# power.net
KiCad netlist of a schematic drawn in Altium Designer
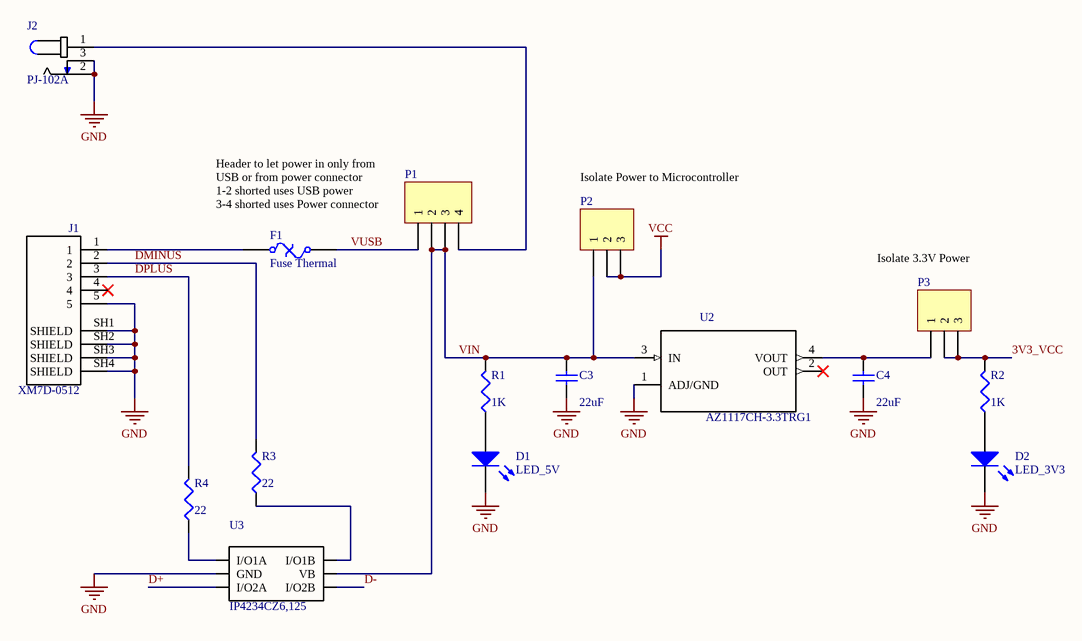
[diagram p0: power.SchDoc]

(export (version "E")
  (design (tool "Eeschema 10.0.6"))
  (components
    (comp (ref "C3")
      (value "22uF")
      (footprint "C1206")
      (description "Capacitor (Semiconductor SIM Model)")
      (fields
        (field (name "DIGIKEYPARTNO") "1276-3300-1-ND")
        (field (name "Comment") "Cap Semi")
        (field (name "PUBLISHER") "Altium Limited")
      )
      (libsource (lib "Miscellaneous Devices") (part "Cap Semi"))
    )
    (comp (ref "C4")
      (value "22uF")
      (footprint "C1206")
      (description "Capacitor (Semiconductor SIM Model)")
      (fields
        (field (name "DIGIKEYPARTNO") "1276-3300-1-ND")
        (field (name "Comment") "Cap Semi")
        (field (name "PUBLISHER") "Altium Limited")
      )
      (libsource (lib "Miscellaneous Devices") (part "Cap Semi"))
    )
    (comp (ref "D1")
      (value "LED_5V")
      (footprint "3.2X1.6X1.1")
      (description "Typical RED, GREEN, YELLOW, AMBER GaAs LED")
      (fields (field (name "PUBLISHER") "Altium Limited"))
      (libsource (lib "Miscellaneous Devices") (part "LED2"))
    )
    (comp (ref "D2")
      (value "LED_3V3")
      (footprint "3.2X1.6X1.1")
      (description "Typical RED, GREEN, YELLOW, AMBER GaAs LED")
      (fields (field (name "PUBLISHER") "Altium Limited"))
      (libsource (lib "Miscellaneous Devices") (part "LED2"))
    )
    (comp (ref "F1")
      (value "Fuse Thermal")
      (footprint "1812")
      (description "Thermal Fuse")
      (fields
        (field (name "MANUFACTURERPARTNO") "MF-MSMF050-2")
        (field (name "DIGIKEYPARTNO") "MF-MSMF050-2CT-ND")
        (field (name "PUBLISHER") "Altium Limited")
      )
      (libsource (lib "Miscellaneous Devices") (part "Fuse Thermal"))
    )
    (comp (ref "J1")
      (value "XM7D-0512")
      (footprint "*OMRON_XM7D-0512_XM7D-0512(Primary)")
      (description "Conn Mini USB Type B SKT 5 POS 0.8mm Solder RA Thru-Hole 5 Terminal 1 Port")
      (fields (field (name "MF") "Omron Electronics"))
      (libsource (lib "XM7D-0512") (part "XM7D-0512"))
    )
    (comp (ref "J2")
      (value "PJ-102A")
      (footprint "*CUI_PJ-102A")
      (description "2.0 mm Center Pin, 2.5 A, Right Angle, Through Hole, Tapered Pins, Dc Power Jack Connector")
      (fields (field (name "MF") "CUI Inc."))
      (libsource (lib "PJ-102A") (part "PJ-102A"))
    )
    (comp (ref "P1")
      (value "Header 4")
      (footprint "HDR1X4")
      (description "Header, 4-Pin")
      (fields (field (name "PUBLISHER") "Altium Limited"))
      (libsource (lib "Miscellaneous Connectors") (part "Header 4"))
    )
    (comp (ref "P2")
      (value "ON   OFF")
      (footprint "HDR1X3")
      (description "Header, 3-Pin")
      (fields (field (name "PUBLISHER") "Altium Limited"))
      (libsource (lib "Miscellaneous Connectors") (part "Header 3"))
    )
    (comp (ref "P3")
      (value "3.3 NC")
      (footprint "HDR1X3")
      (description "Header, 3-Pin")
      (fields (field (name "PUBLISHER") "Altium Limited"))
      (libsource (lib "Miscellaneous Connectors") (part "Header 3"))
    )
    (comp (ref "R1")
      (value "1K")
      (footprint "C1206")
      (description "Resistor")
      (fields (field (name "Comment") "Res3") (field (name "PUBLISHER") "Altium Limited"))
      (libsource (lib "Miscellaneous Devices") (part "Res3"))
    )
    (comp (ref "R2")
      (value "1K")
      (footprint "C1206")
      (description "Resistor")
      (fields (field (name "Comment") "Res3") (field (name "PUBLISHER") "Altium Limited"))
      (libsource (lib "Miscellaneous Devices") (part "Res3"))
    )
    (comp (ref "R3")
      (value "22")
      (footprint "C1206")
      (description "Resistor")
      (fields (field (name "Comment") "Res3") (field (name "PUBLISHER") "Altium Limited"))
      (libsource (lib "Miscellaneous Devices") (part "Res3"))
    )
    (comp (ref "R4")
      (value "22")
      (footprint "C1206")
      (description "Resistor")
      (fields (field (name "Comment") "Res3") (field (name "PUBLISHER") "Altium Limited"))
      (libsource (lib "Miscellaneous Devices") (part "Res3"))
    )
    (comp (ref "U2")
      (value "AZ1117CH-3.3TRG1")
      (footprint "*SOT230P696X180-4N")
      (description "Voltage stabiliser; LDO, fixed; 3.3V; 0.8A; SOT223; SMD")
      (fields
        (field (name "MF") "Diodes Incorporated")
        (field (name "DIGIKEYPARTNO") "AZ1117CH-3.3TRG1DICT-ND")
      )
      (libsource (lib "LM1117MP-3.3") (part "LM1117MP-3.3"))
    )
    (comp (ref "U3")
      (value "IP4234CZ6,125")
      (footprint "*SOT-457")
      (description "DIODE, ESD TVS, USB2.0, SOT457; Operating Voltage: 3V; No. of Pins: 6; SVHC: No SVHC _18-Jun-2010_")
      (fields (field (name "MF") "NXP Semiconductors"))
      (libsource (lib "IP4234CZ6") (part "IP4234CZ6"))
    )
  )
  (nets
    (net (code "1") (name "/3V3_VCC") (class "Default")
      (node (ref "P3") (pin "2") (pinfunction "2_2") (pintype "passive"))
      (node (ref "P3") (pin "3") (pinfunction "3_3") (pintype "passive"))
      (node (ref "R2") (pin "2") (pinfunction "2_2") (pintype "passive"))
    )
    (net (code "2") (name "/D+") (class "Default")
      (node (ref "U3") (pin "3") (pinfunction "I/O2A_3") (pintype "bidirectional"))
    )
    (net (code "3") (name "/D-") (class "Default")
      (node (ref "U3") (pin "4") (pinfunction "I/O2B_4") (pintype "bidirectional"))
    )
    (net (code "4") (name "/DMINUS") (class "Default")
      (node (ref "J1") (pin "2") (pinfunction "2_2") (pintype "passive"))
      (node (ref "R3") (pin "2") (pinfunction "2_2") (pintype "passive"))
    )
    (net (code "5") (name "/DPLUS") (class "Default")
      (node (ref "J1") (pin "3") (pinfunction "3_3") (pintype "passive"))
      (node (ref "R4") (pin "2") (pinfunction "2_2") (pintype "passive"))
    )
    (net (code "6") (name "/VIN") (class "Default")
      (node (ref "C3") (pin "2") (pinfunction "2_2") (pintype "passive"))
      (node (ref "P1") (pin "2") (pinfunction "2_2") (pintype "passive"))
      (node (ref "P1") (pin "3") (pinfunction "3_3") (pintype "passive"))
      (node (ref "P2") (pin "1") (pinfunction "1_1") (pintype "passive"))
      (node (ref "R1") (pin "2") (pinfunction "2_2") (pintype "passive"))
      (node (ref "U2") (pin "3") (pinfunction "IN_3") (pintype "input"))
      (node (ref "U3") (pin "5") (pinfunction "VB_5") (pintype "bidirectional"))
    )
    (net (code "7") (name "/VUSB") (class "Default")
      (node (ref "F1") (pin "2") (pinfunction "2_2") (pintype "passive"))
      (node (ref "P1") (pin "1") (pinfunction "1_1") (pintype "passive"))
    )
    (net (code "8") (name "GND") (class "Default")
      (node (ref "C3") (pin "1") (pinfunction "1_1") (pintype "passive"))
      (node (ref "C4") (pin "1") (pinfunction "1_1") (pintype "passive"))
      (node (ref "D1") (pin "2") (pinfunction "K_2") (pintype "passive"))
      (node (ref "D2") (pin "2") (pinfunction "K_2") (pintype "passive"))
      (node (ref "J1") (pin "5") (pinfunction "5_5") (pintype "passive"))
      (node (ref "J1") (pin "SH1") (pinfunction "SHIELD_SH1") (pintype "passive"))
      (node (ref "J1") (pin "SH2") (pinfunction "SHIELD_SH2") (pintype "passive"))
      (node (ref "J1") (pin "SH3") (pinfunction "SHIELD_SH3") (pintype "passive"))
      (node (ref "J1") (pin "SH4") (pinfunction "SHIELD_SH4") (pintype "passive"))
      (node (ref "J2") (pin "2") (pinfunction "2_2") (pintype "passive"))
      (node (ref "J2") (pin "3") (pinfunction "3_3") (pintype "passive"))
      (node (ref "U2") (pin "1") (pinfunction "ADJ/GND_1") (pintype "passive"))
      (node (ref "U3") (pin "2") (pinfunction "GND_2") (pintype "bidirectional"))
    )
    (net (code "9") (name "Net-(D1-A)") (class "Default")
      (node (ref "D1") (pin "1") (pinfunction "A_1") (pintype "passive"))
      (node (ref "R1") (pin "1") (pinfunction "1_1") (pintype "passive"))
    )
    (net (code "10") (name "Net-(D2-A)") (class "Default")
      (node (ref "D2") (pin "1") (pinfunction "A_1") (pintype "passive"))
      (node (ref "R2") (pin "1") (pinfunction "1_1") (pintype "passive"))
    )
    (net (code "11") (name "Net-(F1-Pad1)") (class "Default")
      (node (ref "F1") (pin "1") (pinfunction "1_1") (pintype "passive"))
      (node (ref "J1") (pin "1") (pinfunction "1_1") (pintype "passive"))
    )
    (net (code "12") (name "Net-(J2-Pad1)") (class "Default")
      (node (ref "J2") (pin "1") (pinfunction "1_1") (pintype "passive"))
      (node (ref "P1") (pin "4") (pinfunction "4_4") (pintype "passive"))
    )
    (net (code "13") (name "Net-(U2-VOUT)") (class "Default")
      (node (ref "C4") (pin "2") (pinfunction "2_2") (pintype "passive"))
      (node (ref "P3") (pin "1") (pinfunction "1_1") (pintype "passive"))
      (node (ref "U2") (pin "4") (pinfunction "VOUT_4") (pintype "output"))
    )
    (net (code "14") (name "Net-(U3-I{slash}O1A)") (class "Default")
      (node (ref "R4") (pin "1") (pinfunction "1_1") (pintype "passive"))
      (node (ref "U3") (pin "1") (pinfunction "I/O1A_1") (pintype "bidirectional"))
    )
    (net (code "15") (name "Net-(U3-I{slash}O1B)") (class "Default")
      (node (ref "R3") (pin "1") (pinfunction "1_1") (pintype "passive"))
      (node (ref "U3") (pin "6") (pinfunction "I/O1B_6") (pintype "bidirectional"))
    )
    (net (code "16") (name "VCC") (class "Default")
      (node (ref "P2") (pin "2") (pinfunction "2_2") (pintype "passive"))
      (node (ref "P2") (pin "3") (pinfunction "3_3") (pintype "passive"))
    )
    (net (code "17") (name "unconnected-(J1-Pad4)") (class "Default")
      (node (ref "J1") (pin "4") (pinfunction "4_4") (pintype "passive+no_connect"))
    )
    (net (code "18") (name "unconnected-(U2-OUT-Pad2)") (class "Default")
      (node (ref "U2") (pin "2") (pinfunction "OUT_2") (pintype "output+no_connect"))
    )
  )
)
